# MDM_V3_LEDPad_B.net
KiCad netlist of a schematic drawn in EAGLE
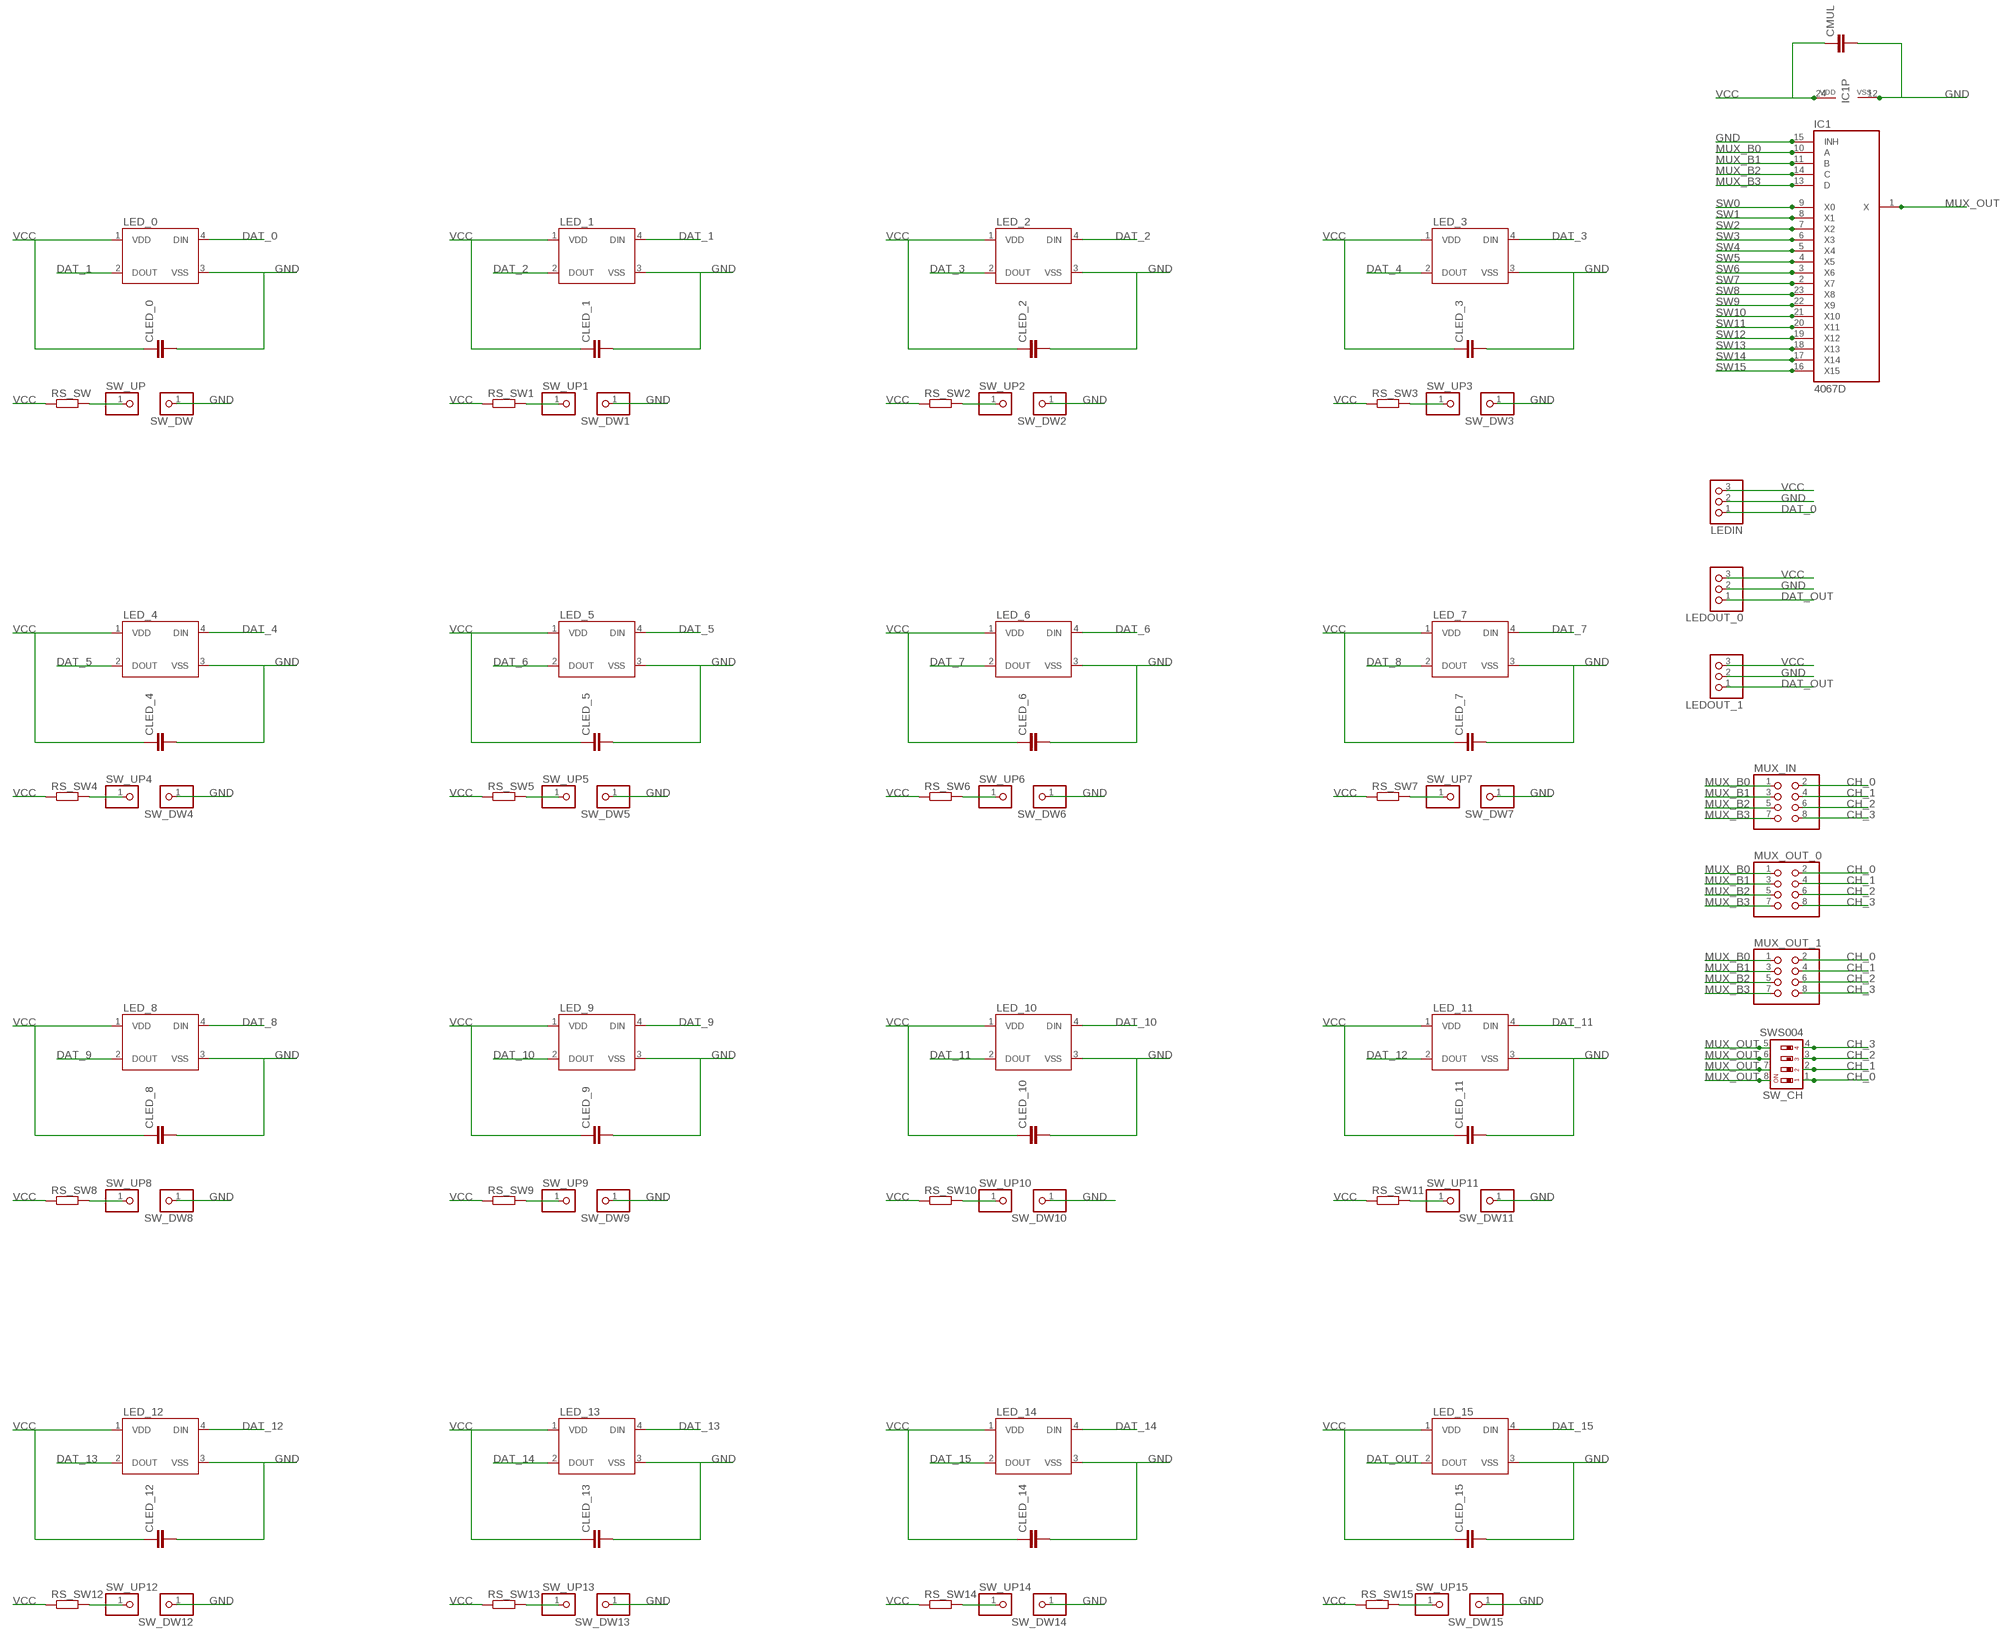
[diagram p0: schematic, sheet 1]

(export (version "E")
  (design (tool "Eeschema 10.0.6"))
  (components
    (comp (ref "CLED_0")
      (value "C-EUC1206K")
      (footprint "eagle-import:C1206K")
      (libsource (lib "eagle-import") (part "C-EUC1206K"))
    )
    (comp (ref "CLED_1")
      (value "C-EUC1206K")
      (footprint "eagle-import:C1206K")
      (libsource (lib "eagle-import") (part "C-EUC1206K"))
    )
    (comp (ref "CLED_2")
      (value "C-EUC1206K")
      (footprint "eagle-import:C1206K")
      (libsource (lib "eagle-import") (part "C-EUC1206K"))
    )
    (comp (ref "CLED_3")
      (value "C-EUC1206K")
      (footprint "eagle-import:C1206K")
      (libsource (lib "eagle-import") (part "C-EUC1206K"))
    )
    (comp (ref "CLED_4")
      (value "C-EUC1206K")
      (footprint "eagle-import:C1206K")
      (libsource (lib "eagle-import") (part "C-EUC1206K"))
    )
    (comp (ref "CLED_5")
      (value "C-EUC1206K")
      (footprint "eagle-import:C1206K")
      (libsource (lib "eagle-import") (part "C-EUC1206K"))
    )
    (comp (ref "CLED_6")
      (value "C-EUC1206K")
      (footprint "eagle-import:C1206K")
      (libsource (lib "eagle-import") (part "C-EUC1206K"))
    )
    (comp (ref "CLED_7")
      (value "C-EUC1206K")
      (footprint "eagle-import:C1206K")
      (libsource (lib "eagle-import") (part "C-EUC1206K"))
    )
    (comp (ref "CLED_8")
      (value "C-EUC1206K")
      (footprint "eagle-import:C1206K")
      (libsource (lib "eagle-import") (part "C-EUC1206K"))
    )
    (comp (ref "CLED_9")
      (value "C-EUC1206K")
      (footprint "eagle-import:C1206K")
      (libsource (lib "eagle-import") (part "C-EUC1206K"))
    )
    (comp (ref "CLED_10")
      (value "C-EUC1206K")
      (footprint "eagle-import:C1206K")
      (libsource (lib "eagle-import") (part "C-EUC1206K"))
    )
    (comp (ref "CLED_11")
      (value "C-EUC1206K")
      (footprint "eagle-import:C1206K")
      (libsource (lib "eagle-import") (part "C-EUC1206K"))
    )
    (comp (ref "CLED_12")
      (value "C-EUC1206K")
      (footprint "eagle-import:C1206K")
      (libsource (lib "eagle-import") (part "C-EUC1206K"))
    )
    (comp (ref "CLED_13")
      (value "C-EUC1206K")
      (footprint "eagle-import:C1206K")
      (libsource (lib "eagle-import") (part "C-EUC1206K"))
    )
    (comp (ref "CLED_14")
      (value "C-EUC1206K")
      (footprint "eagle-import:C1206K")
      (libsource (lib "eagle-import") (part "C-EUC1206K"))
    )
    (comp (ref "CLED_15")
      (value "C-EUC1206K")
      (footprint "eagle-import:C1206K")
      (libsource (lib "eagle-import") (part "C-EUC1206K"))
    )
    (comp (ref "CMUL")
      (value "C-EUC1206K")
      (footprint "eagle-import:C1206K")
      (libsource (lib "eagle-import") (part "C-EUC1206K"))
    )
    (comp (ref "IC1")
      (value "4067D")
      (footprint "eagle-import:SO24W")
      (libsource (lib "eagle-import") (part "4067D"))
    )
    (comp (ref "LEDIN")
      (value "PINHD-1X3")
      (footprint "eagle-import:1X03")
      (libsource (lib "eagle-import") (part "PINHD-1X3"))
    )
    (comp (ref "LEDOUT_0")
      (value "PINHD-1X3")
      (footprint "eagle-import:1X03")
      (libsource (lib "eagle-import") (part "PINHD-1X3"))
    )
    (comp (ref "LEDOUT_1")
      (value "PINHD-1X3")
      (footprint "eagle-import:1X03")
      (libsource (lib "eagle-import") (part "PINHD-1X3"))
    )
    (comp (ref "LED_0")
      (value "WS2812B")
      (footprint "eagle-import:WS2812B")
      (libsource (lib "eagle-import") (part "WS2812B"))
    )
    (comp (ref "LED_1")
      (value "WS2812B")
      (footprint "eagle-import:WS2812B")
      (libsource (lib "eagle-import") (part "WS2812B"))
    )
    (comp (ref "LED_2")
      (value "WS2812B")
      (footprint "eagle-import:WS2812B")
      (libsource (lib "eagle-import") (part "WS2812B"))
    )
    (comp (ref "LED_3")
      (value "WS2812B")
      (footprint "eagle-import:WS2812B")
      (libsource (lib "eagle-import") (part "WS2812B"))
    )
    (comp (ref "LED_4")
      (value "WS2812B")
      (footprint "eagle-import:WS2812B")
      (libsource (lib "eagle-import") (part "WS2812B"))
    )
    (comp (ref "LED_5")
      (value "WS2812B")
      (footprint "eagle-import:WS2812B")
      (libsource (lib "eagle-import") (part "WS2812B"))
    )
    (comp (ref "LED_6")
      (value "WS2812B")
      (footprint "eagle-import:WS2812B")
      (libsource (lib "eagle-import") (part "WS2812B"))
    )
    (comp (ref "LED_7")
      (value "WS2812B")
      (footprint "eagle-import:WS2812B")
      (libsource (lib "eagle-import") (part "WS2812B"))
    )
    (comp (ref "LED_8")
      (value "WS2812B")
      (footprint "eagle-import:WS2812B")
      (libsource (lib "eagle-import") (part "WS2812B"))
    )
    (comp (ref "LED_9")
      (value "WS2812B")
      (footprint "eagle-import:WS2812B")
      (libsource (lib "eagle-import") (part "WS2812B"))
    )
    (comp (ref "LED_10")
      (value "WS2812B")
      (footprint "eagle-import:WS2812B")
      (libsource (lib "eagle-import") (part "WS2812B"))
    )
    (comp (ref "LED_11")
      (value "WS2812B")
      (footprint "eagle-import:WS2812B")
      (libsource (lib "eagle-import") (part "WS2812B"))
    )
    (comp (ref "LED_12")
      (value "WS2812B")
      (footprint "eagle-import:WS2812B")
      (libsource (lib "eagle-import") (part "WS2812B"))
    )
    (comp (ref "LED_13")
      (value "WS2812B")
      (footprint "eagle-import:WS2812B")
      (libsource (lib "eagle-import") (part "WS2812B"))
    )
    (comp (ref "LED_14")
      (value "WS2812B")
      (footprint "eagle-import:WS2812B")
      (libsource (lib "eagle-import") (part "WS2812B"))
    )
    (comp (ref "LED_15")
      (value "WS2812B")
      (footprint "eagle-import:WS2812B")
      (libsource (lib "eagle-import") (part "WS2812B"))
    )
    (comp (ref "MUX_IN")
      (value "PINHD-2X4")
      (footprint "eagle-import:2X04")
      (libsource (lib "eagle-import") (part "PINHD-2X4"))
    )
    (comp (ref "MUX_OUT_0")
      (value "PINHD-2X4")
      (footprint "eagle-import:2X04")
      (libsource (lib "eagle-import") (part "PINHD-2X4"))
    )
    (comp (ref "MUX_OUT_1")
      (value "PINHD-2X4")
      (footprint "eagle-import:2X04")
      (libsource (lib "eagle-import") (part "PINHD-2X4"))
    )
    (comp (ref "RS_SW")
      (value "R-EU_R1206")
      (footprint "eagle-import:R1206")
      (libsource (lib "eagle-import") (part "R-EU_R1206"))
    )
    (comp (ref "RS_SW1")
      (value "R-EU_R1206")
      (footprint "eagle-import:R1206")
      (libsource (lib "eagle-import") (part "R-EU_R1206"))
    )
    (comp (ref "RS_SW2")
      (value "R-EU_R1206")
      (footprint "eagle-import:R1206")
      (libsource (lib "eagle-import") (part "R-EU_R1206"))
    )
    (comp (ref "RS_SW3")
      (value "R-EU_R1206")
      (footprint "eagle-import:R1206")
      (libsource (lib "eagle-import") (part "R-EU_R1206"))
    )
    (comp (ref "RS_SW4")
      (value "R-EU_R1206")
      (footprint "eagle-import:R1206")
      (libsource (lib "eagle-import") (part "R-EU_R1206"))
    )
    (comp (ref "RS_SW5")
      (value "R-EU_R1206")
      (footprint "eagle-import:R1206")
      (libsource (lib "eagle-import") (part "R-EU_R1206"))
    )
    (comp (ref "RS_SW6")
      (value "R-EU_R1206")
      (footprint "eagle-import:R1206")
      (libsource (lib "eagle-import") (part "R-EU_R1206"))
    )
    (comp (ref "RS_SW7")
      (value "R-EU_R1206")
      (footprint "eagle-import:R1206")
      (libsource (lib "eagle-import") (part "R-EU_R1206"))
    )
    (comp (ref "RS_SW8")
      (value "R-EU_R1206")
      (footprint "eagle-import:R1206")
      (libsource (lib "eagle-import") (part "R-EU_R1206"))
    )
    (comp (ref "RS_SW9")
      (value "R-EU_R1206")
      (footprint "eagle-import:R1206")
      (libsource (lib "eagle-import") (part "R-EU_R1206"))
    )
    (comp (ref "RS_SW10")
      (value "R-EU_R1206")
      (footprint "eagle-import:R1206")
      (libsource (lib "eagle-import") (part "R-EU_R1206"))
    )
    (comp (ref "RS_SW11")
      (value "R-EU_R1206")
      (footprint "eagle-import:R1206")
      (libsource (lib "eagle-import") (part "R-EU_R1206"))
    )
    (comp (ref "RS_SW12")
      (value "R-EU_R1206")
      (footprint "eagle-import:R1206")
      (libsource (lib "eagle-import") (part "R-EU_R1206"))
    )
    (comp (ref "RS_SW13")
      (value "R-EU_R1206")
      (footprint "eagle-import:R1206")
      (libsource (lib "eagle-import") (part "R-EU_R1206"))
    )
    (comp (ref "RS_SW14")
      (value "R-EU_R1206")
      (footprint "eagle-import:R1206")
      (libsource (lib "eagle-import") (part "R-EU_R1206"))
    )
    (comp (ref "RS_SW15")
      (value "R-EU_R1206")
      (footprint "eagle-import:R1206")
      (libsource (lib "eagle-import") (part "R-EU_R1206"))
    )
    (comp (ref "SW_CH")
      (value "SWS004")
      (footprint "eagle-import:SMS-004")
      (libsource (lib "eagle-import") (part "SWS004"))
    )
    (comp (ref "SW_DW")
      (value "PINHD-1X1CB")
      (footprint "eagle-import:1X01-CLEANBIG")
      (libsource (lib "eagle-import") (part "PINHD-1X1CB"))
    )
    (comp (ref "SW_DW1")
      (value "PINHD-1X1CB")
      (footprint "eagle-import:1X01-CLEANBIG")
      (libsource (lib "eagle-import") (part "PINHD-1X1CB"))
    )
    (comp (ref "SW_DW2")
      (value "PINHD-1X1CB")
      (footprint "eagle-import:1X01-CLEANBIG")
      (libsource (lib "eagle-import") (part "PINHD-1X1CB"))
    )
    (comp (ref "SW_DW3")
      (value "PINHD-1X1CB")
      (footprint "eagle-import:1X01-CLEANBIG")
      (libsource (lib "eagle-import") (part "PINHD-1X1CB"))
    )
    (comp (ref "SW_DW4")
      (value "PINHD-1X1CB")
      (footprint "eagle-import:1X01-CLEANBIG")
      (libsource (lib "eagle-import") (part "PINHD-1X1CB"))
    )
    (comp (ref "SW_DW5")
      (value "PINHD-1X1CB")
      (footprint "eagle-import:1X01-CLEANBIG")
      (libsource (lib "eagle-import") (part "PINHD-1X1CB"))
    )
    (comp (ref "SW_DW6")
      (value "PINHD-1X1CB")
      (footprint "eagle-import:1X01-CLEANBIG")
      (libsource (lib "eagle-import") (part "PINHD-1X1CB"))
    )
    (comp (ref "SW_DW7")
      (value "PINHD-1X1CB")
      (footprint "eagle-import:1X01-CLEANBIG")
      (libsource (lib "eagle-import") (part "PINHD-1X1CB"))
    )
    (comp (ref "SW_DW8")
      (value "PINHD-1X1CB")
      (footprint "eagle-import:1X01-CLEANBIG")
      (libsource (lib "eagle-import") (part "PINHD-1X1CB"))
    )
    (comp (ref "SW_DW9")
      (value "PINHD-1X1CB")
      (footprint "eagle-import:1X01-CLEANBIG")
      (libsource (lib "eagle-import") (part "PINHD-1X1CB"))
    )
    (comp (ref "SW_DW10")
      (value "PINHD-1X1CB")
      (footprint "eagle-import:1X01-CLEANBIG")
      (libsource (lib "eagle-import") (part "PINHD-1X1CB"))
    )
    (comp (ref "SW_DW11")
      (value "PINHD-1X1CB")
      (footprint "eagle-import:1X01-CLEANBIG")
      (libsource (lib "eagle-import") (part "PINHD-1X1CB"))
    )
    (comp (ref "SW_DW12")
      (value "PINHD-1X1CB")
      (footprint "eagle-import:1X01-CLEANBIG")
      (libsource (lib "eagle-import") (part "PINHD-1X1CB"))
    )
    (comp (ref "SW_DW13")
      (value "PINHD-1X1CB")
      (footprint "eagle-import:1X01-CLEANBIG")
      (libsource (lib "eagle-import") (part "PINHD-1X1CB"))
    )
    (comp (ref "SW_DW14")
      (value "PINHD-1X1CB")
      (footprint "eagle-import:1X01-CLEANBIG")
      (libsource (lib "eagle-import") (part "PINHD-1X1CB"))
    )
    (comp (ref "SW_DW15")
      (value "PINHD-1X1CB")
      (footprint "eagle-import:1X01-CLEANBIG")
      (libsource (lib "eagle-import") (part "PINHD-1X1CB"))
    )
    (comp (ref "SW_UP")
      (value "PINHD-1X1CB")
      (footprint "eagle-import:1X01-CLEANBIG")
      (libsource (lib "eagle-import") (part "PINHD-1X1CB"))
    )
    (comp (ref "SW_UP1")
      (value "PINHD-1X1CB")
      (footprint "eagle-import:1X01-CLEANBIG")
      (libsource (lib "eagle-import") (part "PINHD-1X1CB"))
    )
    (comp (ref "SW_UP2")
      (value "PINHD-1X1CB")
      (footprint "eagle-import:1X01-CLEANBIG")
      (libsource (lib "eagle-import") (part "PINHD-1X1CB"))
    )
    (comp (ref "SW_UP3")
      (value "PINHD-1X1CB")
      (footprint "eagle-import:1X01-CLEANBIG")
      (libsource (lib "eagle-import") (part "PINHD-1X1CB"))
    )
    (comp (ref "SW_UP4")
      (value "PINHD-1X1CB")
      (footprint "eagle-import:1X01-CLEANBIG")
      (libsource (lib "eagle-import") (part "PINHD-1X1CB"))
    )
    (comp (ref "SW_UP5")
      (value "PINHD-1X1CB")
      (footprint "eagle-import:1X01-CLEANBIG")
      (libsource (lib "eagle-import") (part "PINHD-1X1CB"))
    )
    (comp (ref "SW_UP6")
      (value "PINHD-1X1CB")
      (footprint "eagle-import:1X01-CLEANBIG")
      (libsource (lib "eagle-import") (part "PINHD-1X1CB"))
    )
    (comp (ref "SW_UP7")
      (value "PINHD-1X1CB")
      (footprint "eagle-import:1X01-CLEANBIG")
      (libsource (lib "eagle-import") (part "PINHD-1X1CB"))
    )
    (comp (ref "SW_UP8")
      (value "PINHD-1X1CB")
      (footprint "eagle-import:1X01-CLEANBIG")
      (libsource (lib "eagle-import") (part "PINHD-1X1CB"))
    )
    (comp (ref "SW_UP9")
      (value "PINHD-1X1CB")
      (footprint "eagle-import:1X01-CLEANBIG")
      (libsource (lib "eagle-import") (part "PINHD-1X1CB"))
    )
    (comp (ref "SW_UP10")
      (value "PINHD-1X1CB")
      (footprint "eagle-import:1X01-CLEANBIG")
      (libsource (lib "eagle-import") (part "PINHD-1X1CB"))
    )
    (comp (ref "SW_UP11")
      (value "PINHD-1X1CB")
      (footprint "eagle-import:1X01-CLEANBIG")
      (libsource (lib "eagle-import") (part "PINHD-1X1CB"))
    )
    (comp (ref "SW_UP12")
      (value "PINHD-1X1CB")
      (footprint "eagle-import:1X01-CLEANBIG")
      (libsource (lib "eagle-import") (part "PINHD-1X1CB"))
    )
    (comp (ref "SW_UP13")
      (value "PINHD-1X1CB")
      (footprint "eagle-import:1X01-CLEANBIG")
      (libsource (lib "eagle-import") (part "PINHD-1X1CB"))
    )
    (comp (ref "SW_UP14")
      (value "PINHD-1X1CB")
      (footprint "eagle-import:1X01-CLEANBIG")
      (libsource (lib "eagle-import") (part "PINHD-1X1CB"))
    )
    (comp (ref "SW_UP15")
      (value "PINHD-1X1CB")
      (footprint "eagle-import:1X01-CLEANBIG")
      (libsource (lib "eagle-import") (part "PINHD-1X1CB"))
    )
  )
  (nets
    (net (code "1") (name "/CH_0") (class "Default")
      (node (ref "MUX_IN") (pin "2") (pinfunction "2_2") (pintype "passive"))
      (node (ref "MUX_OUT_0") (pin "2") (pinfunction "2_2") (pintype "passive"))
      (node (ref "MUX_OUT_1") (pin "2") (pinfunction "2_2") (pintype "passive"))
      (node (ref "SW_CH") (pin "1") (pinfunction "1_1") (pintype "passive"))
    )
    (net (code "2") (name "/CH_1") (class "Default")
      (node (ref "MUX_IN") (pin "4") (pinfunction "4_4") (pintype "passive"))
      (node (ref "MUX_OUT_0") (pin "4") (pinfunction "4_4") (pintype "passive"))
      (node (ref "MUX_OUT_1") (pin "4") (pinfunction "4_4") (pintype "passive"))
      (node (ref "SW_CH") (pin "2") (pinfunction "2_2") (pintype "passive"))
    )
    (net (code "3") (name "/CH_2") (class "Default")
      (node (ref "MUX_IN") (pin "6") (pinfunction "6_6") (pintype "passive"))
      (node (ref "MUX_OUT_0") (pin "6") (pinfunction "6_6") (pintype "passive"))
      (node (ref "MUX_OUT_1") (pin "6") (pinfunction "6_6") (pintype "passive"))
      (node (ref "SW_CH") (pin "3") (pinfunction "3_3") (pintype "passive"))
    )
    (net (code "4") (name "/CH_3") (class "Default")
      (node (ref "MUX_IN") (pin "8") (pinfunction "8_8") (pintype "passive"))
      (node (ref "MUX_OUT_0") (pin "8") (pinfunction "8_8") (pintype "passive"))
      (node (ref "MUX_OUT_1") (pin "8") (pinfunction "8_8") (pintype "passive"))
      (node (ref "SW_CH") (pin "4") (pinfunction "4_4") (pintype "passive"))
    )
    (net (code "5") (name "/DAT_0") (class "Default")
      (node (ref "LEDIN") (pin "1") (pinfunction "1_1") (pintype "passive"))
      (node (ref "LED_0") (pin "4") (pinfunction "DIN_4") (pintype "input"))
    )
    (net (code "6") (name "/DAT_1") (class "Default")
      (node (ref "LED_0") (pin "2") (pinfunction "DOUT_2") (pintype "output"))
      (node (ref "LED_1") (pin "4") (pinfunction "DIN_4") (pintype "input"))
    )
    (net (code "7") (name "/DAT_2") (class "Default")
      (node (ref "LED_1") (pin "2") (pinfunction "DOUT_2") (pintype "output"))
      (node (ref "LED_2") (pin "4") (pinfunction "DIN_4") (pintype "input"))
    )
    (net (code "8") (name "/DAT_3") (class "Default")
      (node (ref "LED_2") (pin "2") (pinfunction "DOUT_2") (pintype "output"))
      (node (ref "LED_3") (pin "4") (pinfunction "DIN_4") (pintype "input"))
    )
    (net (code "9") (name "/DAT_4") (class "Default")
      (node (ref "LED_3") (pin "2") (pinfunction "DOUT_2") (pintype "output"))
      (node (ref "LED_4") (pin "4") (pinfunction "DIN_4") (pintype "input"))
    )
    (net (code "10") (name "/DAT_5") (class "Default")
      (node (ref "LED_4") (pin "2") (pinfunction "DOUT_2") (pintype "output"))
      (node (ref "LED_5") (pin "4") (pinfunction "DIN_4") (pintype "input"))
    )
    (net (code "11") (name "/DAT_6") (class "Default")
      (node (ref "LED_5") (pin "2") (pinfunction "DOUT_2") (pintype "output"))
      (node (ref "LED_6") (pin "4") (pinfunction "DIN_4") (pintype "input"))
    )
    (net (code "12") (name "/DAT_7") (class "Default")
      (node (ref "LED_6") (pin "2") (pinfunction "DOUT_2") (pintype "output"))
      (node (ref "LED_7") (pin "4") (pinfunction "DIN_4") (pintype "input"))
    )
    (net (code "13") (name "/DAT_8") (class "Default")
      (node (ref "LED_7") (pin "2") (pinfunction "DOUT_2") (pintype "output"))
      (node (ref "LED_8") (pin "4") (pinfunction "DIN_4") (pintype "input"))
    )
    (net (code "14") (name "/DAT_9") (class "Default")
      (node (ref "LED_8") (pin "2") (pinfunction "DOUT_2") (pintype "output"))
      (node (ref "LED_9") (pin "4") (pinfunction "DIN_4") (pintype "input"))
    )
    (net (code "15") (name "/DAT_10") (class "Default")
      (node (ref "LED_10") (pin "4") (pinfunction "DIN_4") (pintype "input"))
      (node (ref "LED_9") (pin "2") (pinfunction "DOUT_2") (pintype "output"))
    )
    (net (code "16") (name "/DAT_11") (class "Default")
      (node (ref "LED_10") (pin "2") (pinfunction "DOUT_2") (pintype "output"))
      (node (ref "LED_11") (pin "4") (pinfunction "DIN_4") (pintype "input"))
    )
    (net (code "17") (name "/DAT_12") (class "Default")
      (node (ref "LED_11") (pin "2") (pinfunction "DOUT_2") (pintype "output"))
      (node (ref "LED_12") (pin "4") (pinfunction "DIN_4") (pintype "input"))
    )
    (net (code "18") (name "/DAT_13") (class "Default")
      (node (ref "LED_12") (pin "2") (pinfunction "DOUT_2") (pintype "output"))
      (node (ref "LED_13") (pin "4") (pinfunction "DIN_4") (pintype "input"))
    )
    (net (code "19") (name "/DAT_14") (class "Default")
      (node (ref "LED_13") (pin "2") (pinfunction "DOUT_2") (pintype "output"))
      (node (ref "LED_14") (pin "4") (pinfunction "DIN_4") (pintype "input"))
    )
    (net (code "20") (name "/DAT_15") (class "Default")
      (node (ref "LED_14") (pin "2") (pinfunction "DOUT_2") (pintype "output"))
      (node (ref "LED_15") (pin "4") (pinfunction "DIN_4") (pintype "input"))
    )
    (net (code "21") (name "/DAT_OUT") (class "Default")
      (node (ref "LEDOUT_0") (pin "1") (pinfunction "1_1") (pintype "passive"))
      (node (ref "LEDOUT_1") (pin "1") (pinfunction "1_1") (pintype "passive"))
      (node (ref "LED_15") (pin "2") (pinfunction "DOUT_2") (pintype "output"))
    )
    (net (code "22") (name "/GND") (class "Default")
      (node (ref "CLED_0") (pin "2") (pinfunction "2_2") (pintype "passive"))
      (node (ref "CLED_1") (pin "2") (pinfunction "2_2") (pintype "passive"))
      (node (ref "CLED_10") (pin "2") (pinfunction "2_2") (pintype "passive"))
      (node (ref "CLED_11") (pin "2") (pinfunction "2_2") (pintype "passive"))
      (node (ref "CLED_12") (pin "2") (pinfunction "2_2") (pintype "passive"))
      (node (ref "CLED_13") (pin "2") (pinfunction "2_2") (pintype "passive"))
      (node (ref "CLED_14") (pin "2") (pinfunction "2_2") (pintype "passive"))
      (node (ref "CLED_15") (pin "2") (pinfunction "2_2") (pintype "passive"))
      (node (ref "CLED_2") (pin "2") (pinfunction "2_2") (pintype "passive"))
      (node (ref "CLED_3") (pin "2") (pinfunction "2_2") (pintype "passive"))
      (node (ref "CLED_4") (pin "2") (pinfunction "2_2") (pintype "passive"))
      (node (ref "CLED_5") (pin "2") (pinfunction "2_2") (pintype "passive"))
      (node (ref "CLED_6") (pin "2") (pinfunction "2_2") (pintype "passive"))
      (node (ref "CLED_7") (pin "2") (pinfunction "2_2") (pintype "passive"))
      (node (ref "CLED_8") (pin "2") (pinfunction "2_2") (pintype "passive"))
      (node (ref "CLED_9") (pin "2") (pinfunction "2_2") (pintype "passive"))
      (node (ref "CMUL") (pin "2") (pinfunction "2_2") (pintype "passive"))
      (node (ref "IC1") (pin "12") (pinfunction "VSS_12") (pintype "power_in"))
      (node (ref "IC1") (pin "15") (pinfunction "INH_15") (pintype "input"))
      (node (ref "LEDIN") (pin "2") (pinfunction "2_2") (pintype "passive"))
      (node (ref "LEDOUT_0") (pin "2") (pinfunction "2_2") (pintype "passive"))
      (node (ref "LEDOUT_1") (pin "2") (pinfunction "2_2") (pintype "passive"))
      (node (ref "LED_0") (pin "3") (pinfunction "VSS_3") (pintype "power_in"))
      (node (ref "LED_1") (pin "3") (pinfunction "VSS_3") (pintype "power_in"))
      (node (ref "LED_10") (pin "3") (pinfunction "VSS_3") (pintype "power_in"))
      (node (ref "LED_11") (pin "3") (pinfunction "VSS_3") (pintype "power_in"))
      (node (ref "LED_12") (pin "3") (pinfunction "VSS_3") (pintype "power_in"))
      (node (ref "LED_13") (pin "3") (pinfunction "VSS_3") (pintype "power_in"))
      (node (ref "LED_14") (pin "3") (pinfunction "VSS_3") (pintype "power_in"))
      (node (ref "LED_15") (pin "3") (pinfunction "VSS_3") (pintype "power_in"))
      (node (ref "LED_2") (pin "3") (pinfunction "VSS_3") (pintype "power_in"))
      (node (ref "LED_3") (pin "3") (pinfunction "VSS_3") (pintype "power_in"))
      (node (ref "LED_4") (pin "3") (pinfunction "VSS_3") (pintype "power_in"))
      (node (ref "LED_5") (pin "3") (pinfunction "VSS_3") (pintype "power_in"))
      (node (ref "LED_6") (pin "3") (pinfunction "VSS_3") (pintype "power_in"))
      (node (ref "LED_7") (pin "3") (pinfunction "VSS_3") (pintype "power_in"))
      (node (ref "LED_8") (pin "3") (pinfunction "VSS_3") (pintype "power_in"))
      (node (ref "LED_9") (pin "3") (pinfunction "VSS_3") (pintype "power_in"))
      (node (ref "SW_DW") (pin "1") (pinfunction "1_1") (pintype "passive"))
      (node (ref "SW_DW1") (pin "1") (pinfunction "1_1") (pintype "passive"))
      (node (ref "SW_DW10") (pin "1") (pinfunction "1_1") (pintype "passive"))
      (node (ref "SW_DW11") (pin "1") (pinfunction "1_1") (pintype "passive"))
      (node (ref "SW_DW12") (pin "1") (pinfunction "1_1") (pintype "passive"))
      (node (ref "SW_DW13") (pin "1") (pinfunction "1_1") (pintype "passive"))
      (node (ref "SW_DW14") (pin "1") (pinfunction "1_1") (pintype "passive"))
      (node (ref "SW_DW15") (pin "1") (pinfunction "1_1") (pintype "passive"))
      (node (ref "SW_DW2") (pin "1") (pinfunction "1_1") (pintype "passive"))
      (node (ref "SW_DW3") (pin "1") (pinfunction "1_1") (pintype "passive"))
      (node (ref "SW_DW4") (pin "1") (pinfunction "1_1") (pintype "passive"))
      (node (ref "SW_DW5") (pin "1") (pinfunction "1_1") (pintype "passive"))
      (node (ref "SW_DW6") (pin "1") (pinfunction "1_1") (pintype "passive"))
      (node (ref "SW_DW7") (pin "1") (pinfunction "1_1") (pintype "passive"))
      (node (ref "SW_DW8") (pin "1") (pinfunction "1_1") (pintype "passive"))
      (node (ref "SW_DW9") (pin "1") (pinfunction "1_1") (pintype "passive"))
    )
    (net (code "23") (name "/MUX_B0") (class "Default")
      (node (ref "IC1") (pin "10") (pinfunction "A_10") (pintype "input"))
      (node (ref "MUX_IN") (pin "1") (pinfunction "1_1") (pintype "passive"))
      (node (ref "MUX_OUT_0") (pin "1") (pinfunction "1_1") (pintype "passive"))
      (node (ref "MUX_OUT_1") (pin "1") (pinfunction "1_1") (pintype "passive"))
    )
    (net (code "24") (name "/MUX_B1") (class "Default")
      (node (ref "IC1") (pin "11") (pinfunction "B_11") (pintype "input"))
      (node (ref "MUX_IN") (pin "3") (pinfunction "3_3") (pintype "passive"))
      (node (ref "MUX_OUT_0") (pin "3") (pinfunction "3_3") (pintype "passive"))
      (node (ref "MUX_OUT_1") (pin "3") (pinfunction "3_3") (pintype "passive"))
    )
    (net (code "25") (name "/MUX_B2") (class "Default")
      (node (ref "IC1") (pin "14") (pinfunction "C_14") (pintype "input"))
      (node (ref "MUX_IN") (pin "5") (pinfunction "5_5") (pintype "passive"))
      (node (ref "MUX_OUT_0") (pin "5") (pinfunction "5_5") (pintype "passive"))
      (node (ref "MUX_OUT_1") (pin "5") (pinfunction "5_5") (pintype "passive"))
    )
    (net (code "26") (name "/MUX_B3") (class "Default")
      (node (ref "IC1") (pin "13") (pinfunction "D_13") (pintype "input"))
      (node (ref "MUX_IN") (pin "7") (pinfunction "7_7") (pintype "passive"))
      (node (ref "MUX_OUT_0") (pin "7") (pinfunction "7_7") (pintype "passive"))
      (node (ref "MUX_OUT_1") (pin "7") (pinfunction "7_7") (pintype "passive"))
    )
    (net (code "27") (name "/MUX_OUT") (class "Default")
      (node (ref "IC1") (pin "1") (pinfunction "X_1") (pintype "output"))
      (node (ref "SW_CH") (pin "5") (pinfunction "5_5") (pintype "passive"))
      (node (ref "SW_CH") (pin "6") (pinfunction "6_6") (pintype "passive"))
      (node (ref "SW_CH") (pin "7") (pinfunction "7_7") (pintype "passive"))
      (node (ref "SW_CH") (pin "8") (pinfunction "8_8") (pintype "passive"))
    )
    (net (code "28") (name "/SW0") (class "Default")
      (node (ref "IC1") (pin "9") (pinfunction "X0_9") (pintype "input"))
      (node (ref "RS_SW") (pin "2") (pinfunction "2_2") (pintype "passive"))
      (node (ref "SW_UP") (pin "1") (pinfunction "1_1") (pintype "passive"))
    )
    (net (code "29") (name "/SW1") (class "Default")
      (node (ref "IC1") (pin "8") (pinfunction "X1_8") (pintype "input"))
      (node (ref "RS_SW1") (pin "2") (pinfunction "2_2") (pintype "passive"))
      (node (ref "SW_UP1") (pin "1") (pinfunction "1_1") (pintype "passive"))
    )
    (net (code "30") (name "/SW2") (class "Default")
      (node (ref "IC1") (pin "7") (pinfunction "X2_7") (pintype "input"))
      (node (ref "RS_SW2") (pin "2") (pinfunction "2_2") (pintype "passive"))
      (node (ref "SW_UP2") (pin "1") (pinfunction "1_1") (pintype "passive"))
    )
    (net (code "31") (name "/SW3") (class "Default")
      (node (ref "IC1") (pin "6") (pinfunction "X3_6") (pintype "input"))
      (node (ref "RS_SW3") (pin "2") (pinfunction "2_2") (pintype "passive"))
      (node (ref "SW_UP3") (pin "1") (pinfunction "1_1") (pintype "passive"))
    )
    (net (code "32") (name "/SW4") (class "Default")
      (node (ref "IC1") (pin "5") (pinfunction "X4_5") (pintype "input"))
      (node (ref "RS_SW4") (pin "2") (pinfunction "2_2") (pintype "passive"))
      (node (ref "SW_UP4") (pin "1") (pinfunction "1_1") (pintype "passive"))
    )
    (net (code "33") (name "/SW5") (class "Default")
      (node (ref "IC1") (pin "4") (pinfunction "X5_4") (pintype "input"))
      (node (ref "RS_SW5") (pin "2") (pinfunction "2_2") (pintype "passive"))
      (node (ref "SW_UP5") (pin "1") (pinfunction "1_1") (pintype "passive"))
    )
    (net (code "34") (name "/SW6") (class "Default")
      (node (ref "IC1") (pin "3") (pinfunction "X6_3") (pintype "input"))
      (node (ref "RS_SW6") (pin "2") (pinfunction "2_2") (pintype "passive"))
      (node (ref "SW_UP6") (pin "1") (pinfunction "1_1") (pintype "passive"))
    )
    (net (code "35") (name "/SW7") (class "Default")
      (node (ref "IC1") (pin "2") (pinfunction "X7_2") (pintype "input"))
      (node (ref "RS_SW7") (pin "2") (pinfunction "2_2") (pintype "passive"))
      (node (ref "SW_UP7") (pin "1") (pinfunction "1_1") (pintype "passive"))
    )
    (net (code "36") (name "/SW8") (class "Default")
      (node (ref "IC1") (pin "23") (pinfunction "X8_23") (pintype "input"))
      (node (ref "RS_SW8") (pin "2") (pinfunction "2_2") (pintype "passive"))
      (node (ref "SW_UP8") (pin "1") (pinfunction "1_1") (pintype "passive"))
    )
    (net (code "37") (name "/SW9") (class "Default")
      (node (ref "IC1") (pin "22") (pinfunction "X9_22") (pintype "input"))
      (node (ref "RS_SW9") (pin "2") (pinfunction "2_2") (pintype "passive"))
      (node (ref "SW_UP9") (pin "1") (pinfunction "1_1") (pintype "passive"))
    )
    (net (code "38") (name "/SW10") (class "Default")
      (node (ref "IC1") (pin "21") (pinfunction "X10_21") (pintype "input"))
      (node (ref "RS_SW10") (pin "2") (pinfunction "2_2") (pintype "passive"))
      (node (ref "SW_UP10") (pin "1") (pinfunction "1_1") (pintype "passive"))
    )
    (net (code "39") (name "/SW11") (class "Default")
      (node (ref "IC1") (pin "20") (pinfunction "X11_20") (pintype "input"))
      (node (ref "RS_SW11") (pin "2") (pinfunction "2_2") (pintype "passive"))
      (node (ref "SW_UP11") (pin "1") (pinfunction "1_1") (pintype "passive"))
    )
    (net (code "40") (name "/SW12") (class "Default")
      (node (ref "IC1") (pin "19") (pinfunction "X12_19") (pintype "input"))
      (node (ref "RS_SW12") (pin "2") (pinfunction "2_2") (pintype "passive"))
      (node (ref "SW_UP12") (pin "1") (pinfunction "1_1") (pintype "passive"))
    )
    (net (code "41") (name "/SW13") (class "Default")
      (node (ref "IC1") (pin "18") (pinfunction "X13_18") (pintype "input"))
      (node (ref "RS_SW13") (pin "2") (pinfunction "2_2") (pintype "passive"))
      (node (ref "SW_UP13") (pin "1") (pinfunction "1_1") (pintype "passive"))
    )
    (net (code "42") (name "/SW14") (class "Default")
      (node (ref "IC1") (pin "17") (pinfunction "X14_17") (pintype "input"))
      (node (ref "RS_SW14") (pin "2") (pinfunction "2_2") (pintype "passive"))
      (node (ref "SW_UP14") (pin "1") (pinfunction "1_1") (pintype "passive"))
    )
    (net (code "43") (name "/SW15") (class "Default")
      (node (ref "IC1") (pin "16") (pinfunction "X15_16") (pintype "input"))
      (node (ref "RS_SW15") (pin "2") (pinfunction "2_2") (pintype "passive"))
      (node (ref "SW_UP15") (pin "1") (pinfunction "1_1") (pintype "passive"))
    )
    (net (code "44") (name "/VCC") (class "Default")
      (node (ref "CLED_0") (pin "1") (pinfunction "1_1") (pintype "passive"))
      (node (ref "CLED_1") (pin "1") (pinfunction "1_1") (pintype "passive"))
      (node (ref "CLED_10") (pin "1") (pinfunction "1_1") (pintype "passive"))
      (node (ref "CLED_11") (pin "1") (pinfunction "1_1") (pintype "passive"))
      (node (ref "CLED_12") (pin "1") (pinfunction "1_1") (pintype "passive"))
      (node (ref "CLED_13") (pin "1") (pinfunction "1_1") (pintype "passive"))
      (node (ref "CLED_14") (pin "1") (pinfunction "1_1") (pintype "passive"))
      (node (ref "CLED_15") (pin "1") (pinfunction "1_1") (pintype "passive"))
      (node (ref "CLED_2") (pin "1") (pinfunction "1_1") (pintype "passive"))
      (node (ref "CLED_3") (pin "1") (pinfunction "1_1") (pintype "passive"))
      (node (ref "CLED_4") (pin "1") (pinfunction "1_1") (pintype "passive"))
      (node (ref "CLED_5") (pin "1") (pinfunction "1_1") (pintype "passive"))
      (node (ref "CLED_6") (pin "1") (pinfunction "1_1") (pintype "passive"))
      (node (ref "CLED_7") (pin "1") (pinfunction "1_1") (pintype "passive"))
      (node (ref "CLED_8") (pin "1") (pinfunction "1_1") (pintype "passive"))
      (node (ref "CLED_9") (pin "1") (pinfunction "1_1") (pintype "passive"))
      (node (ref "CMUL") (pin "1") (pinfunction "1_1") (pintype "passive"))
      (node (ref "IC1") (pin "24") (pinfunction "VDD_24") (pintype "power_in"))
      (node (ref "LEDIN") (pin "3") (pinfunction "3_3") (pintype "passive"))
      (node (ref "LEDOUT_0") (pin "3") (pinfunction "3_3") (pintype "passive"))
      (node (ref "LEDOUT_1") (pin "3") (pinfunction "3_3") (pintype "passive"))
      (node (ref "LED_0") (pin "1") (pinfunction "VDD_1") (pintype "power_in"))
      (node (ref "LED_1") (pin "1") (pinfunction "VDD_1") (pintype "power_in"))
      (node (ref "LED_10") (pin "1") (pinfunction "VDD_1") (pintype "power_in"))
      (node (ref "LED_11") (pin "1") (pinfunction "VDD_1") (pintype "power_in"))
      (node (ref "LED_12") (pin "1") (pinfunction "VDD_1") (pintype "power_in"))
      (node (ref "LED_13") (pin "1") (pinfunction "VDD_1") (pintype "power_in"))
      (node (ref "LED_14") (pin "1") (pinfunction "VDD_1") (pintype "power_in"))
      (node (ref "LED_15") (pin "1") (pinfunction "VDD_1") (pintype "power_in"))
      (node (ref "LED_2") (pin "1") (pinfunction "VDD_1") (pintype "power_in"))
      (node (ref "LED_3") (pin "1") (pinfunction "VDD_1") (pintype "power_in"))
      (node (ref "LED_4") (pin "1") (pinfunction "VDD_1") (pintype "power_in"))
      (node (ref "LED_5") (pin "1") (pinfunction "VDD_1") (pintype "power_in"))
      (node (ref "LED_6") (pin "1") (pinfunction "VDD_1") (pintype "power_in"))
      (node (ref "LED_7") (pin "1") (pinfunction "VDD_1") (pintype "power_in"))
      (node (ref "LED_8") (pin "1") (pinfunction "VDD_1") (pintype "power_in"))
      (node (ref "LED_9") (pin "1") (pinfunction "VDD_1") (pintype "power_in"))
      (node (ref "RS_SW") (pin "1") (pinfunction "1_1") (pintype "passive"))
      (node (ref "RS_SW1") (pin "1") (pinfunction "1_1") (pintype "passive"))
      (node (ref "RS_SW10") (pin "1") (pinfunction "1_1") (pintype "passive"))
      (node (ref "RS_SW11") (pin "1") (pinfunction "1_1") (pintype "passive"))
      (node (ref "RS_SW12") (pin "1") (pinfunction "1_1") (pintype "passive"))
      (node (ref "RS_SW13") (pin "1") (pinfunction "1_1") (pintype "passive"))
      (node (ref "RS_SW14") (pin "1") (pinfunction "1_1") (pintype "passive"))
      (node (ref "RS_SW15") (pin "1") (pinfunction "1_1") (pintype "passive"))
      (node (ref "RS_SW2") (pin "1") (pinfunction "1_1") (pintype "passive"))
      (node (ref "RS_SW3") (pin "1") (pinfunction "1_1") (pintype "passive"))
      (node (ref "RS_SW4") (pin "1") (pinfunction "1_1") (pintype "passive"))
      (node (ref "RS_SW5") (pin "1") (pinfunction "1_1") (pintype "passive"))
      (node (ref "RS_SW6") (pin "1") (pinfunction "1_1") (pintype "passive"))
      (node (ref "RS_SW7") (pin "1") (pinfunction "1_1") (pintype "passive"))
      (node (ref "RS_SW8") (pin "1") (pinfunction "1_1") (pintype "passive"))
      (node (ref "RS_SW9") (pin "1") (pinfunction "1_1") (pintype "passive"))
    )
  )
)
